# MiniKey.net
KiCad netlist of a schematic drawn in Altium Designer
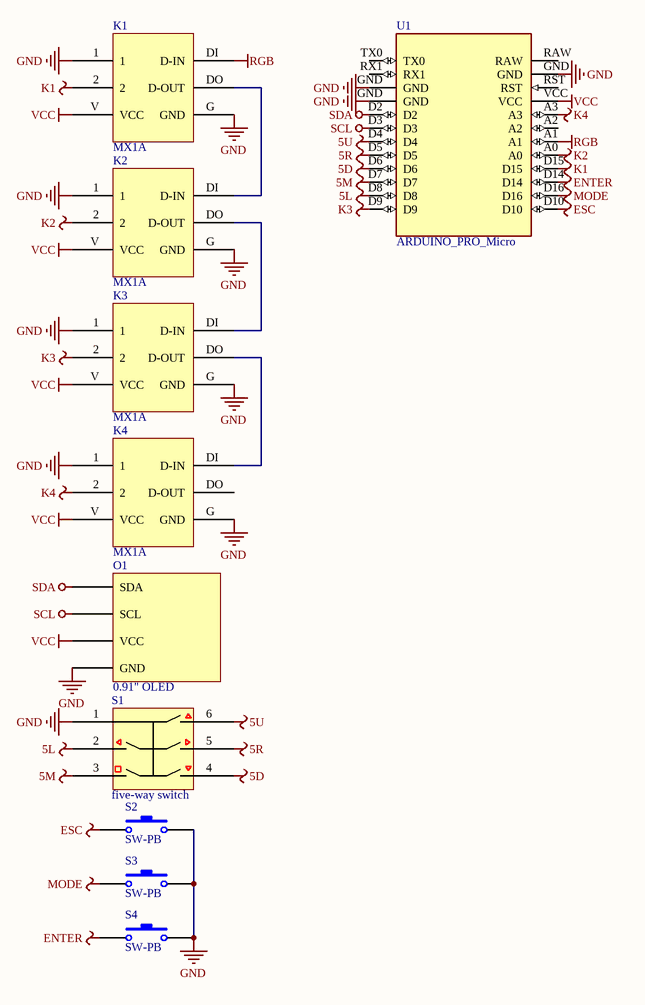
[diagram p0: MiniKey.SchDoc]

(export (version "E")
  (design (tool "Eeschema 10.0.6"))
  (components
    (comp (ref "K1") (value "MX1A") (footprint "MX1A") (libsource (lib "MX1A") (part "MX1A")))
    (comp (ref "K2") (value "MX1A") (footprint "MX1A") (libsource (lib "MX1A") (part "MX1A")))
    (comp (ref "K3") (value "MX1A") (footprint "MX1A") (libsource (lib "MX1A") (part "MX1A")))
    (comp (ref "K4") (value "MX1A") (footprint "MX1A") (libsource (lib "MX1A") (part "MX1A")))
    (comp (ref "O1")
      (value "0.91\" OLED")
      (footprint "0.91-OLED")
      (libsource (lib "0.91-OLED") (part "0.91{dblquote} OLED"))
    )
    (comp (ref "S1")
      (value "five-way switch")
      (footprint "five-way switch")
      (libsource (lib "five-way switch") (part "five-way switch"))
    )
    (comp (ref "S2")
      (value "SW-PB")
      (footprint "SW_PB2_A1")
      (description "峚雄羲壽")
      (fields (field (name "PUBLISHER") "Altium Limited"))
      (libsource (lib "Fszhang") (part "SW-PB"))
    )
    (comp (ref "S3")
      (value "SW-PB")
      (footprint "SW_PB2_A1")
      (description "峚雄羲壽")
      (fields (field (name "PUBLISHER") "Altium Limited"))
      (libsource (lib "Fszhang") (part "SW-PB"))
    )
    (comp (ref "S4")
      (value "SW-PB")
      (footprint "SW_PB2_A1")
      (description "峚雄羲壽")
      (fields (field (name "PUBLISHER") "Altium Limited"))
      (libsource (lib "Fszhang") (part "SW-PB"))
    )
    (comp (ref "U1")
      (value "ARDUINO_PRO_Micro")
      (footprint "MODULE_ARDUINO_PRO_MINI")
      (description "ATmega328 Arduino Pro Mini 328 5V/16MHz AVRÂ® ATmega AVR MCU 8-Bit Embedded Evaluation Board")
      (fields (field (name "MP") "ARDUINO PRO MINI") (field (name "MF") "SparkFun Electronics"))
      (libsource (lib "ARDUINO_PRO_Micro") (part "ARDUINO_PRO_Micro"))
    )
  )
  (nets
    (net (code "1") (name "5D") (class "Default")
      (node (ref "S1") (pin "4") (pinfunction "4_4") (pintype "passive"))
      (node (ref "U1") (pin "D6") (pinfunction "D6_D6") (pintype "bidirectional"))
    )
    (net (code "2") (name "5L") (class "Default")
      (node (ref "S1") (pin "2") (pinfunction "2_2") (pintype "passive"))
      (node (ref "U1") (pin "D8") (pinfunction "D8_D8") (pintype "bidirectional"))
    )
    (net (code "3") (name "5M") (class "Default")
      (node (ref "S1") (pin "3") (pinfunction "3_3") (pintype "passive"))
      (node (ref "U1") (pin "D7") (pinfunction "D7_D7") (pintype "bidirectional"))
    )
    (net (code "4") (name "5R") (class "Default")
      (node (ref "S1") (pin "5") (pinfunction "5_5") (pintype "passive"))
      (node (ref "U1") (pin "D5") (pinfunction "D5_D5") (pintype "bidirectional"))
    )
    (net (code "5") (name "5U") (class "Default")
      (node (ref "S1") (pin "6") (pinfunction "6_6") (pintype "passive"))
      (node (ref "U1") (pin "D4") (pinfunction "D4_D4") (pintype "bidirectional"))
    )
    (net (code "6") (name "ENTER") (class "Default")
      (node (ref "S4") (pin "1") (pinfunction "1_1") (pintype "passive"))
      (node (ref "U1") (pin "D14") (pinfunction "D14_D14") (pintype "bidirectional"))
    )
    (net (code "7") (name "ESC") (class "Default")
      (node (ref "S2") (pin "1") (pinfunction "1_1") (pintype "passive"))
      (node (ref "U1") (pin "D10") (pinfunction "D10_D10") (pintype "bidirectional"))
    )
    (net (code "8") (name "GND") (class "Default")
      (node (ref "K1") (pin "1") (pinfunction "1_1") (pintype "passive"))
      (node (ref "K1") (pin "G") (pinfunction "GND_G") (pintype "passive"))
      (node (ref "K2") (pin "1") (pinfunction "1_1") (pintype "passive"))
      (node (ref "K2") (pin "G") (pinfunction "GND_G") (pintype "passive"))
      (node (ref "K3") (pin "1") (pinfunction "1_1") (pintype "passive"))
      (node (ref "K3") (pin "G") (pinfunction "GND_G") (pintype "passive"))
      (node (ref "K4") (pin "1") (pinfunction "1_1") (pintype "passive"))
      (node (ref "K4") (pin "G") (pinfunction "GND_G") (pintype "passive"))
      (node (ref "O1") (pin "GND") (pinfunction "GND_GND") (pintype "passive"))
      (node (ref "S1") (pin "1") (pinfunction "1_1") (pintype "passive"))
      (node (ref "S2") (pin "2") (pinfunction "2_2") (pintype "passive"))
      (node (ref "S3") (pin "2") (pinfunction "2_2") (pintype "passive"))
      (node (ref "S4") (pin "2") (pinfunction "2_2") (pintype "passive"))
      (node (ref "U1") (pin "GND") (pinfunction "GND_GND") (pintype "open_collector"))
    )
    (net (code "9") (name "K1") (class "Default")
      (node (ref "K1") (pin "2") (pinfunction "2_2") (pintype "passive"))
      (node (ref "U1") (pin "D15") (pinfunction "D15_D15") (pintype "bidirectional"))
    )
    (net (code "10") (name "K2") (class "Default")
      (node (ref "K2") (pin "2") (pinfunction "2_2") (pintype "passive"))
      (node (ref "U1") (pin "A0") (pinfunction "A0_A0") (pintype "bidirectional"))
    )
    (net (code "11") (name "K3") (class "Default")
      (node (ref "K3") (pin "2") (pinfunction "2_2") (pintype "passive"))
      (node (ref "U1") (pin "D9") (pinfunction "D9_D9") (pintype "bidirectional"))
    )
    (net (code "12") (name "K4") (class "Default")
      (node (ref "K4") (pin "2") (pinfunction "2_2") (pintype "passive"))
      (node (ref "U1") (pin "A3") (pinfunction "A3_A3") (pintype "bidirectional"))
    )
    (net (code "13") (name "MODE") (class "Default")
      (node (ref "S3") (pin "1") (pinfunction "1_1") (pintype "passive"))
      (node (ref "U1") (pin "D16") (pinfunction "D16_D16") (pintype "bidirectional"))
    )
    (net (code "14") (name "Net-(K1-D-OUT)") (class "Default")
      (node (ref "K1") (pin "DO") (pinfunction "D-OUT_DO") (pintype "passive"))
      (node (ref "K2") (pin "DI") (pinfunction "D-IN_DI") (pintype "passive"))
    )
    (net (code "15") (name "Net-(K2-D-OUT)") (class "Default")
      (node (ref "K2") (pin "DO") (pinfunction "D-OUT_DO") (pintype "passive"))
      (node (ref "K3") (pin "DI") (pinfunction "D-IN_DI") (pintype "passive"))
    )
    (net (code "16") (name "Net-(K3-D-OUT)") (class "Default")
      (node (ref "K3") (pin "DO") (pinfunction "D-OUT_DO") (pintype "passive"))
      (node (ref "K4") (pin "DI") (pinfunction "D-IN_DI") (pintype "passive"))
    )
    (net (code "17") (name "RGB") (class "Default")
      (node (ref "K1") (pin "DI") (pinfunction "D-IN_DI") (pintype "passive"))
      (node (ref "U1") (pin "A1") (pinfunction "A1_A1") (pintype "bidirectional"))
    )
    (net (code "18") (name "SCL") (class "Default")
      (node (ref "O1") (pin "SCL") (pinfunction "SCL_SCL") (pintype "passive"))
      (node (ref "U1") (pin "D3") (pinfunction "D3_D3") (pintype "bidirectional"))
    )
    (net (code "19") (name "SDA") (class "Default")
      (node (ref "O1") (pin "SDA") (pinfunction "SDA_SDA") (pintype "passive"))
      (node (ref "U1") (pin "D2") (pinfunction "D2_D2") (pintype "bidirectional"))
    )
    (net (code "20") (name "VCC") (class "Default")
      (node (ref "K1") (pin "V") (pinfunction "VCC_V") (pintype "passive"))
      (node (ref "K2") (pin "V") (pinfunction "VCC_V") (pintype "passive"))
      (node (ref "K3") (pin "V") (pinfunction "VCC_V") (pintype "passive"))
      (node (ref "K4") (pin "V") (pinfunction "VCC_V") (pintype "passive"))
      (node (ref "O1") (pin "VCC") (pinfunction "VCC_VCC") (pintype "passive"))
      (node (ref "U1") (pin "VCC") (pinfunction "VCC_VCC") (pintype "power_in"))
    )
    (net (code "21") (name "unconnected-(K4-D-OUT-PadDO)") (class "Default")
      (node (ref "K4") (pin "DO") (pinfunction "D-OUT_DO") (pintype "passive"))
    )
    (net (code "22") (name "unconnected-(U1-PadA2)") (class "Default")
      (node (ref "U1") (pin "A2") (pinfunction "A2_A2") (pintype "bidirectional"))
    )
    (net (code "23") (name "unconnected-(U1-PadRAW)") (class "Default")
      (node (ref "U1") (pin "RAW") (pinfunction "RAW_RAW") (pintype "power_in"))
    )
    (net (code "24") (name "unconnected-(U1-PadRST)") (class "Default")
      (node (ref "U1") (pin "RST") (pinfunction "RST_RST") (pintype "input"))
    )
    (net (code "25") (name "unconnected-(U1-PadRX1)") (class "Default")
      (node (ref "U1") (pin "RX1") (pinfunction "RX1_RX1") (pintype "bidirectional"))
    )
    (net (code "26") (name "unconnected-(U1-PadTX0)") (class "Default")
      (node (ref "U1") (pin "TX0") (pinfunction "TX0_TX0") (pintype "bidirectional"))
    )
  )
)
